# SCH_SmartPark_2023-12-14.net
KiCad netlist of a schematic drawn in EasyEDA
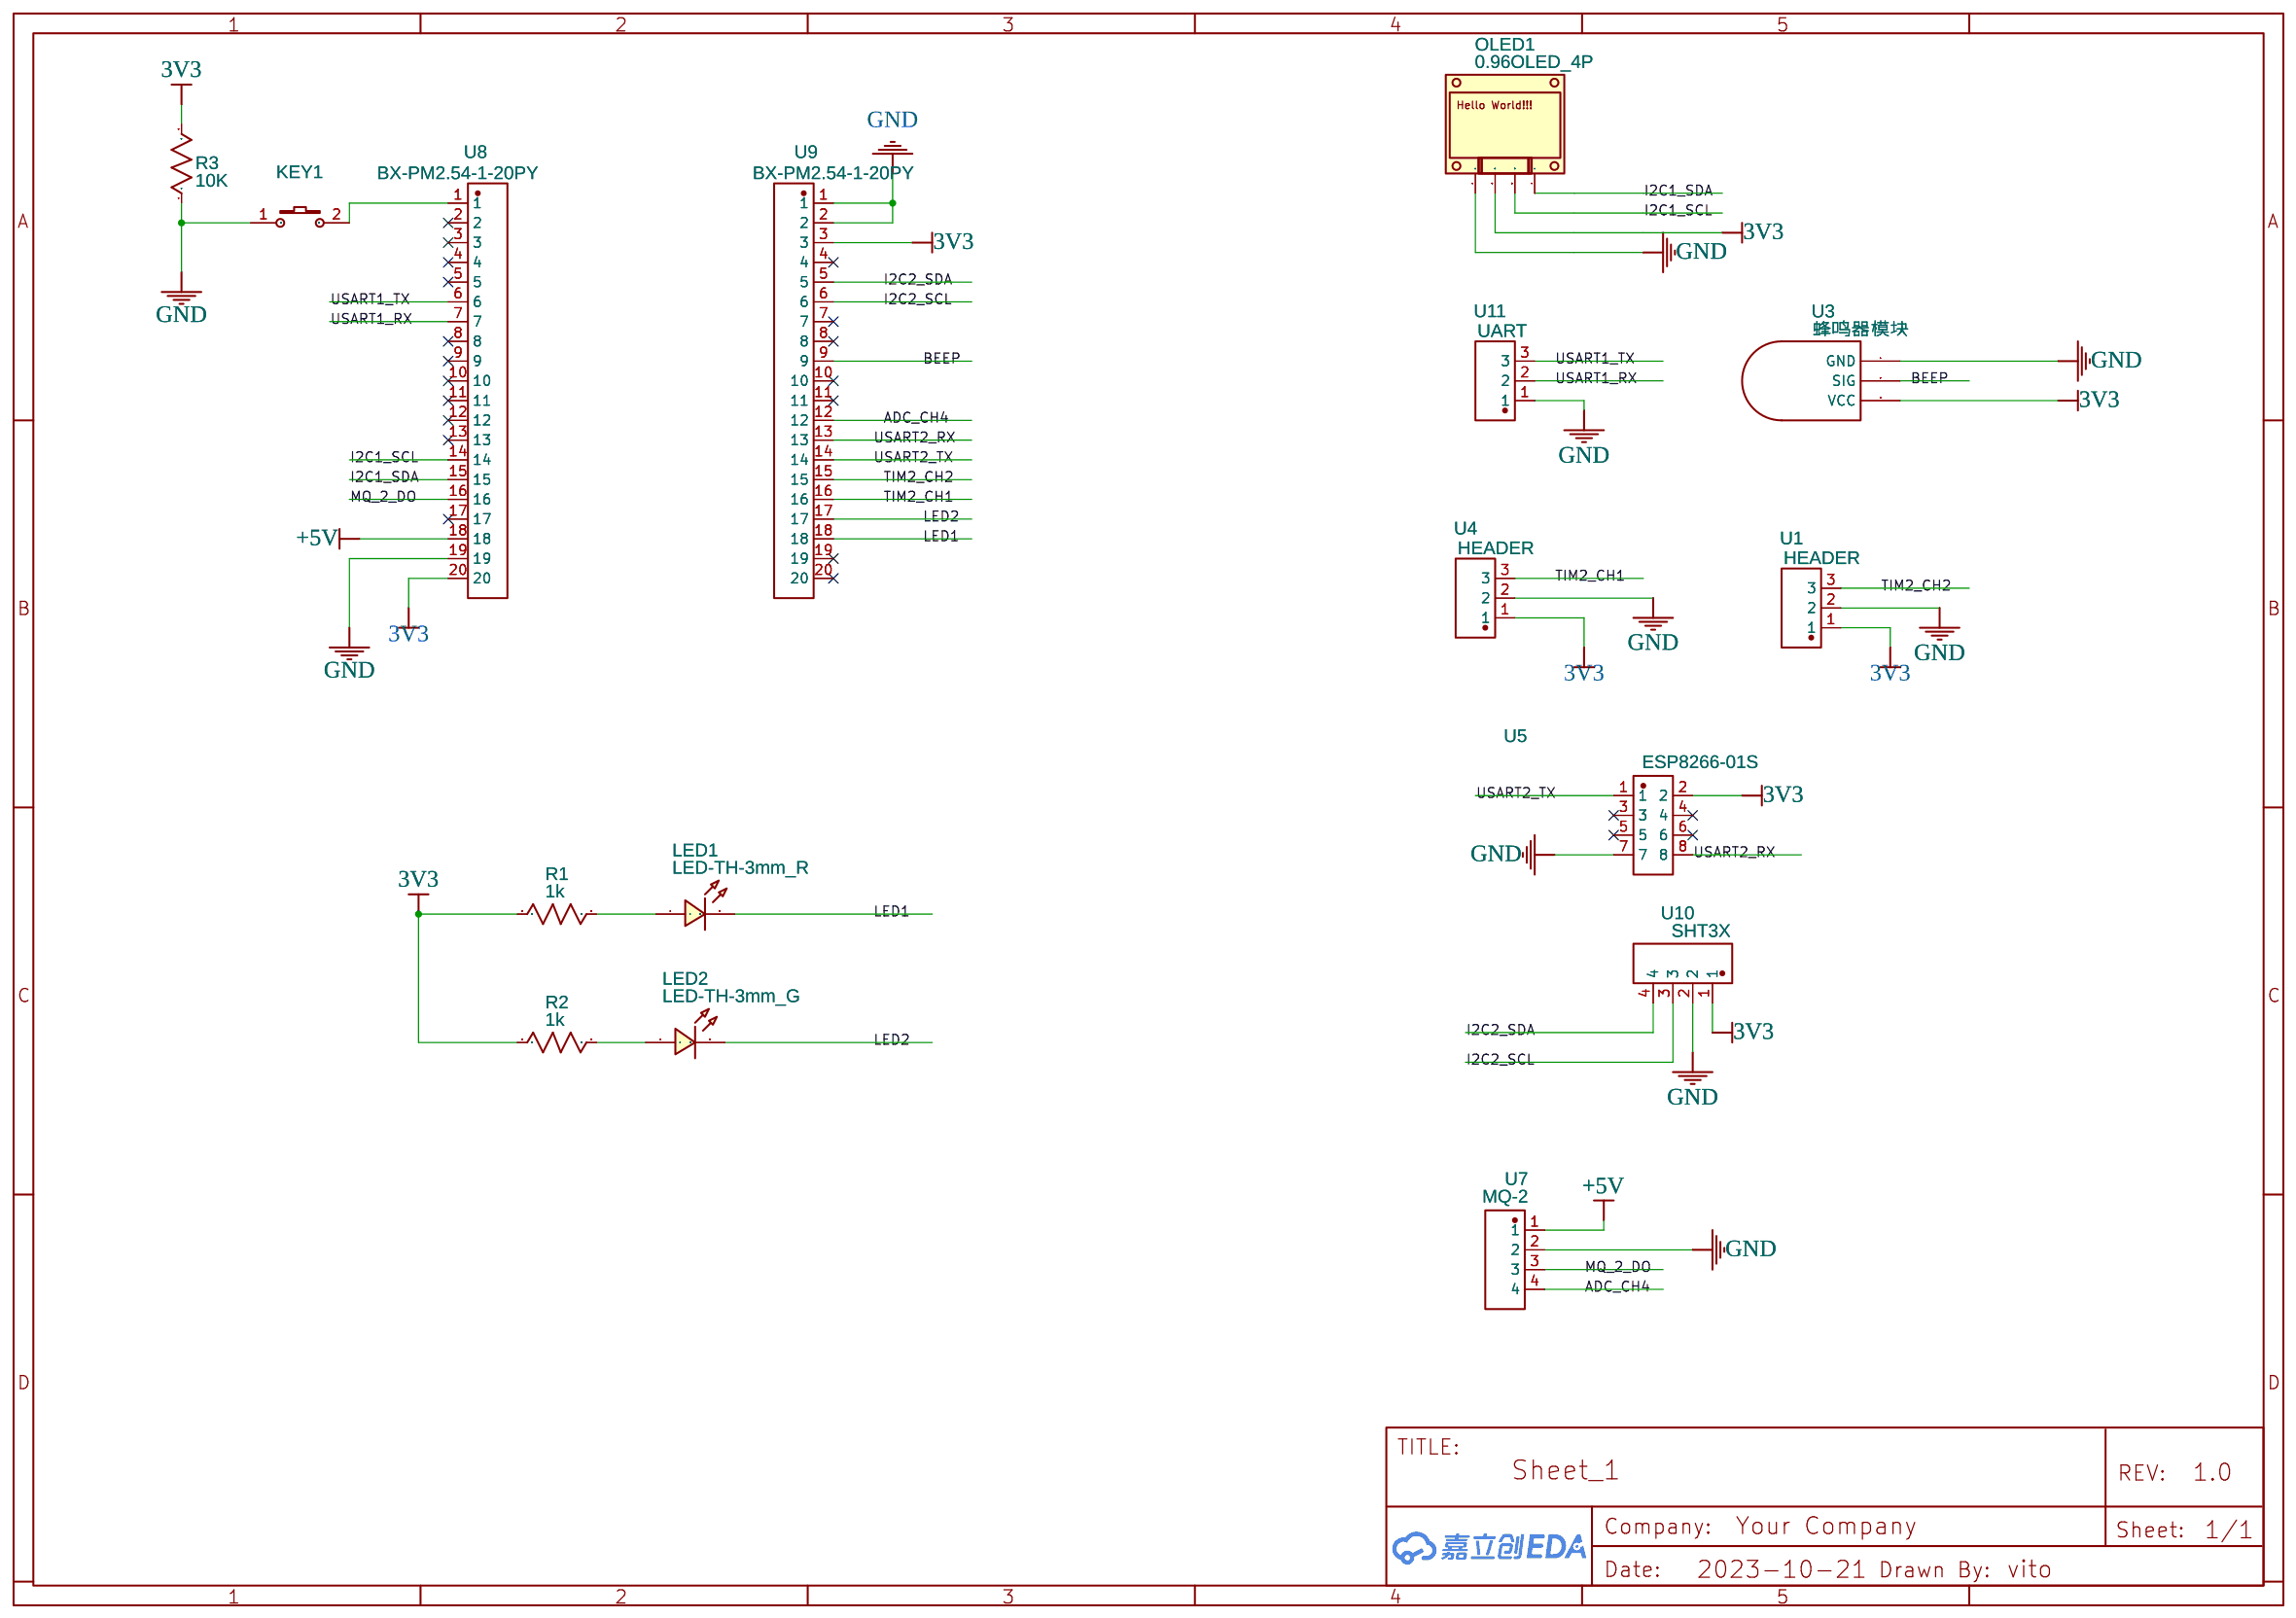
[diagram p0: schematic sheet]

(export (version "E")
  (design (tool "Eeschema 10.0.6"))
  (components
    (comp (ref "KEY1")
      (value "K2-3.6×6.1_SMD")
      (fields (field (name "Manufacturer Part") "K2-1107ST-A4SW-06"))
      (libsource (lib "") (part "K2-3.6×6.1_SMD"))
    )
    (comp (ref "LED1")
      (value "LED-TH-3mm_R")
      (fields
        (field (name "Manufacturer Part") "204-10SDRD/S530-A3-L")
        (field (name "Manufacturer") "EVERLIGHT(台湾亿光)")
      )
      (libsource (lib "") (part "LED-TH-3mm_R"))
    )
    (comp (ref "LED2")
      (value "LED-TH-3mm_G")
      (fields
        (field (name "Manufacturer Part") "204-10SYGD/S530-E3")
        (field (name "Manufacturer") "EVERLIGHT(台湾亿光)")
      )
      (libsource (lib "") (part "LED-TH-3mm_G"))
    )
    (comp (ref "OLED1") (value "0.96OLED_4P") (libsource (lib "") (part "0.96OLED_4P")))
    (comp (ref "R1") (value "1k") (libsource (lib "") (part "R_AXIAL-0.4_US")))
    (comp (ref "R2") (value "1k") (libsource (lib "") (part "R_AXIAL-0.4_US")))
    (comp (ref "R3") (value "10K") (libsource (lib "") (part "R_AXIAL-0.4_US_1")))
    (comp (ref "U1")
      (value "HEADER")
      (fields (field (name "Manufacturer Part") "BX-PM2.54-1-3PY") (field (name "Manufacturer") "Bossie(博锡)"))
      (libsource (lib "") (part "BX-PM2.54-1-3PY"))
    )
    (comp (ref "U3") (value "蜂鸣器模块") (libsource (lib "") (part "蜂鸣器模块")))
    (comp (ref "U4")
      (value "HEADER")
      (fields (field (name "Manufacturer Part") "BX-PM2.54-1-3PY") (field (name "Manufacturer") "Bossie(博锡)"))
      (libsource (lib "") (part "BX-PM2.54-1-3PY"))
    )
    (comp (ref "U5")
      (value "ESP8266-01S")
      (fields (field (name "Manufacturer Part") "ESP8266-TH8"))
      (libsource (lib "") (part "ESP8266-TH8"))
    )
    (comp (ref "U7")
      (value "MQ-2")
      (fields (field (name "Manufacturer Part") "HEADER_1*4P"))
      (libsource (lib "") (part "HEADER_1*4P"))
    )
    (comp (ref "U8")
      (value "BX-PM2.54-1-20PY")
      (fields (field (name "Manufacturer") "Bossie(博锡)"))
      (libsource (lib "") (part "BX-PM2.54-1-20PY_1"))
    )
    (comp (ref "U9")
      (value "BX-PM2.54-1-20PY")
      (fields (field (name "Manufacturer") "Bossie(博锡)"))
      (libsource (lib "") (part "BX-PM2.54-1-20PY"))
    )
    (comp (ref "U10")
      (value "SHT3X")
      (fields (field (name "Manufacturer Part") "HEADER_1*4P"))
      (libsource (lib "") (part "HEADER_1*4P_1"))
    )
    (comp (ref "U11")
      (value "UART")
      (fields (field (name "Manufacturer Part") "BX-PM2.54-1-3PY") (field (name "Manufacturer") "Bossie(博锡)"))
      (libsource (lib "") (part "BX-PM2.54-1-3PY"))
    )
  )
  (nets
    (net (code "1") (name "+5V") (class "Default")
      (node (ref "U7") (pin "1") (pinfunction "1_1") (pintype "unspecified"))
      (node (ref "U8") (pin "18") (pinfunction "18_18") (pintype "unspecified"))
    )
    (net (code "2") (name "/ADC_CH4") (class "Default")
      (node (ref "U7") (pin "4") (pinfunction "4_4") (pintype "unspecified"))
      (node (ref "U9") (pin "12") (pinfunction "12_12") (pintype "unspecified"))
    )
    (net (code "3") (name "/BEEP") (class "Default")
      (node (ref "U3") (pin "2") (pinfunction "SIG_2") (pintype "unspecified"))
      (node (ref "U9") (pin "9") (pinfunction "9_9") (pintype "unspecified"))
    )
    (net (code "4") (name "/I2C1_SCL") (class "Default")
      (node (ref "OLED1") (pin "3") (pinfunction "3_3") (pintype "unspecified"))
      (node (ref "U8") (pin "14") (pinfunction "14_14") (pintype "unspecified"))
    )
    (net (code "5") (name "/I2C1_SDA") (class "Default")
      (node (ref "OLED1") (pin "4") (pinfunction "4_4") (pintype "unspecified"))
      (node (ref "U8") (pin "15") (pinfunction "15_15") (pintype "unspecified"))
    )
    (net (code "6") (name "/I2C2_SCL") (class "Default")
      (node (ref "U10") (pin "3") (pinfunction "3_3") (pintype "unspecified"))
      (node (ref "U9") (pin "6") (pinfunction "6_6") (pintype "unspecified"))
    )
    (net (code "7") (name "/I2C2_SDA") (class "Default")
      (node (ref "U10") (pin "4") (pinfunction "4_4") (pintype "unspecified"))
      (node (ref "U9") (pin "5") (pinfunction "5_5") (pintype "unspecified"))
    )
    (net (code "8") (name "/LED1") (class "Default")
      (node (ref "LED1") (pin "2") (pinfunction "2_2") (pintype "unspecified"))
      (node (ref "U9") (pin "18") (pinfunction "18_18") (pintype "unspecified"))
    )
    (net (code "9") (name "/LED2") (class "Default")
      (node (ref "LED2") (pin "2") (pinfunction "2_2") (pintype "unspecified"))
      (node (ref "U9") (pin "17") (pinfunction "17_17") (pintype "unspecified"))
    )
    (net (code "10") (name "/MQ_2_DO") (class "Default")
      (node (ref "U7") (pin "3") (pinfunction "3_3") (pintype "unspecified"))
      (node (ref "U8") (pin "16") (pinfunction "16_16") (pintype "unspecified"))
    )
    (net (code "11") (name "/TIM2_CH1") (class "Default")
      (node (ref "U4") (pin "3") (pinfunction "3_3") (pintype "unspecified"))
      (node (ref "U9") (pin "16") (pinfunction "16_16") (pintype "unspecified"))
    )
    (net (code "12") (name "/TIM2_CH2") (class "Default")
      (node (ref "U1") (pin "3") (pinfunction "3_3") (pintype "unspecified"))
      (node (ref "U9") (pin "15") (pinfunction "15_15") (pintype "unspecified"))
    )
    (net (code "13") (name "/USART1_RX") (class "Default")
      (node (ref "U11") (pin "2") (pinfunction "2_2") (pintype "unspecified"))
      (node (ref "U8") (pin "7") (pinfunction "7_7") (pintype "unspecified"))
    )
    (net (code "14") (name "/USART1_TX") (class "Default")
      (node (ref "U11") (pin "3") (pinfunction "3_3") (pintype "unspecified"))
      (node (ref "U8") (pin "6") (pinfunction "6_6") (pintype "unspecified"))
    )
    (net (code "15") (name "/USART2_RX") (class "Default")
      (node (ref "U5") (pin "8") (pinfunction "8_8") (pintype "unspecified"))
      (node (ref "U9") (pin "13") (pinfunction "13_13") (pintype "unspecified"))
    )
    (net (code "16") (name "/USART2_TX") (class "Default")
      (node (ref "U5") (pin "1") (pinfunction "1_1") (pintype "unspecified"))
      (node (ref "U9") (pin "14") (pinfunction "14_14") (pintype "unspecified"))
    )
    (net (code "17") (name "3V3") (class "Default")
      (node (ref "OLED1") (pin "2") (pinfunction "2_2") (pintype "unspecified"))
      (node (ref "R1") (pin "1") (pinfunction "1_1") (pintype "unspecified"))
      (node (ref "R2") (pin "1") (pinfunction "1_1") (pintype "unspecified"))
      (node (ref "R3") (pin "2") (pinfunction "2_2") (pintype "unspecified"))
      (node (ref "U1") (pin "1") (pinfunction "1_1") (pintype "unspecified"))
      (node (ref "U10") (pin "1") (pinfunction "1_1") (pintype "unspecified"))
      (node (ref "U3") (pin "3") (pinfunction "VCC_3") (pintype "unspecified"))
      (node (ref "U4") (pin "1") (pinfunction "1_1") (pintype "unspecified"))
      (node (ref "U5") (pin "2") (pinfunction "2_2") (pintype "unspecified"))
      (node (ref "U8") (pin "20") (pinfunction "20_20") (pintype "unspecified"))
      (node (ref "U9") (pin "3") (pinfunction "3_3") (pintype "unspecified"))
    )
    (net (code "18") (name "GND") (class "Default")
      (node (ref "KEY1") (pin "1") (pinfunction "1_1") (pintype "unspecified"))
      (node (ref "OLED1") (pin "1") (pinfunction "1_1") (pintype "unspecified"))
      (node (ref "R3") (pin "1") (pinfunction "1_1") (pintype "unspecified"))
      (node (ref "U1") (pin "2") (pinfunction "2_2") (pintype "unspecified"))
      (node (ref "U10") (pin "2") (pinfunction "2_2") (pintype "unspecified"))
      (node (ref "U11") (pin "1") (pinfunction "1_1") (pintype "unspecified"))
      (node (ref "U3") (pin "1") (pinfunction "GND_1") (pintype "unspecified"))
      (node (ref "U4") (pin "2") (pinfunction "2_2") (pintype "unspecified"))
      (node (ref "U5") (pin "7") (pinfunction "7_7") (pintype "unspecified"))
      (node (ref "U7") (pin "2") (pinfunction "2_2") (pintype "unspecified"))
      (node (ref "U8") (pin "19") (pinfunction "19_19") (pintype "unspecified"))
      (node (ref "U9") (pin "1") (pinfunction "1_1") (pintype "unspecified"))
      (node (ref "U9") (pin "2") (pinfunction "2_2") (pintype "unspecified"))
    )
    (net (code "19") (name "Net-(KEY1-Pad2)") (class "Default")
      (node (ref "KEY1") (pin "2") (pinfunction "2_2") (pintype "unspecified"))
      (node (ref "U8") (pin "1") (pinfunction "1_1") (pintype "unspecified"))
    )
    (net (code "20") (name "Net-(LED1-Pad1)") (class "Default")
      (node (ref "LED1") (pin "1") (pinfunction "1_1") (pintype "unspecified"))
      (node (ref "R1") (pin "2") (pinfunction "2_2") (pintype "unspecified"))
    )
    (net (code "21") (name "Net-(LED2-Pad1)") (class "Default")
      (node (ref "LED2") (pin "1") (pinfunction "1_1") (pintype "unspecified"))
      (node (ref "R2") (pin "2") (pinfunction "2_2") (pintype "unspecified"))
    )
    (net (code "22") (name "unconnected-(U5-Pad3)") (class "Default")
      (node (ref "U5") (pin "3") (pinfunction "3_3") (pintype "unspecified+no_connect"))
    )
    (net (code "23") (name "unconnected-(U5-Pad4)") (class "Default")
      (node (ref "U5") (pin "4") (pinfunction "4_4") (pintype "unspecified+no_connect"))
    )
    (net (code "24") (name "unconnected-(U5-Pad5)") (class "Default")
      (node (ref "U5") (pin "5") (pinfunction "5_5") (pintype "unspecified+no_connect"))
    )
    (net (code "25") (name "unconnected-(U5-Pad6)") (class "Default")
      (node (ref "U5") (pin "6") (pinfunction "6_6") (pintype "unspecified+no_connect"))
    )
    (net (code "26") (name "unconnected-(U8-Pad2)") (class "Default")
      (node (ref "U8") (pin "2") (pinfunction "2_2") (pintype "unspecified+no_connect"))
    )
    (net (code "27") (name "unconnected-(U8-Pad3)") (class "Default")
      (node (ref "U8") (pin "3") (pinfunction "3_3") (pintype "unspecified+no_connect"))
    )
    (net (code "28") (name "unconnected-(U8-Pad4)") (class "Default")
      (node (ref "U8") (pin "4") (pinfunction "4_4") (pintype "unspecified+no_connect"))
    )
    (net (code "29") (name "unconnected-(U8-Pad5)") (class "Default")
      (node (ref "U8") (pin "5") (pinfunction "5_5") (pintype "unspecified+no_connect"))
    )
    (net (code "30") (name "unconnected-(U8-Pad8)") (class "Default")
      (node (ref "U8") (pin "8") (pinfunction "8_8") (pintype "unspecified+no_connect"))
    )
    (net (code "31") (name "unconnected-(U8-Pad9)") (class "Default")
      (node (ref "U8") (pin "9") (pinfunction "9_9") (pintype "unspecified+no_connect"))
    )
    (net (code "32") (name "unconnected-(U8-Pad10)") (class "Default")
      (node (ref "U8") (pin "10") (pinfunction "10_10") (pintype "unspecified+no_connect"))
    )
    (net (code "33") (name "unconnected-(U8-Pad11)") (class "Default")
      (node (ref "U8") (pin "11") (pinfunction "11_11") (pintype "unspecified+no_connect"))
    )
    (net (code "34") (name "unconnected-(U8-Pad12)") (class "Default")
      (node (ref "U8") (pin "12") (pinfunction "12_12") (pintype "unspecified+no_connect"))
    )
    (net (code "35") (name "unconnected-(U8-Pad13)") (class "Default")
      (node (ref "U8") (pin "13") (pinfunction "13_13") (pintype "unspecified+no_connect"))
    )
    (net (code "36") (name "unconnected-(U8-Pad17)") (class "Default")
      (node (ref "U8") (pin "17") (pinfunction "17_17") (pintype "unspecified+no_connect"))
    )
    (net (code "37") (name "unconnected-(U9-Pad4)") (class "Default")
      (node (ref "U9") (pin "4") (pinfunction "4_4") (pintype "unspecified+no_connect"))
    )
    (net (code "38") (name "unconnected-(U9-Pad7)") (class "Default")
      (node (ref "U9") (pin "7") (pinfunction "7_7") (pintype "unspecified+no_connect"))
    )
    (net (code "39") (name "unconnected-(U9-Pad8)") (class "Default")
      (node (ref "U9") (pin "8") (pinfunction "8_8") (pintype "unspecified+no_connect"))
    )
    (net (code "40") (name "unconnected-(U9-Pad10)") (class "Default")
      (node (ref "U9") (pin "10") (pinfunction "10_10") (pintype "unspecified+no_connect"))
    )
    (net (code "41") (name "unconnected-(U9-Pad11)") (class "Default")
      (node (ref "U9") (pin "11") (pinfunction "11_11") (pintype "unspecified+no_connect"))
    )
    (net (code "42") (name "unconnected-(U9-Pad19)") (class "Default")
      (node (ref "U9") (pin "19") (pinfunction "19_19") (pintype "unspecified+no_connect"))
    )
    (net (code "43") (name "unconnected-(U9-Pad20)") (class "Default")
      (node (ref "U9") (pin "20") (pinfunction "20_20") (pintype "unspecified+no_connect"))
    )
  )
)
